# switchesbrd.net
KiCad netlist of a schematic drawn in EAGLE
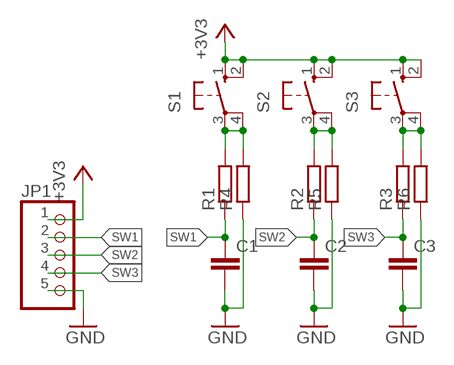
[diagram p0: schematic, sheet 1]

(export (version "E")
  (design (tool "Eeschema 10.0.6"))
  (components
    (comp (ref "C1")
      (value "C-EU025-025X050")
      (footprint "eagle-import:C025-025X050")
      (libsource (lib "eagle-import") (part "C-EU025-025X050"))
    )
    (comp (ref "C2")
      (value "C-EU025-025X050")
      (footprint "eagle-import:C025-025X050")
      (libsource (lib "eagle-import") (part "C-EU025-025X050"))
    )
    (comp (ref "C3")
      (value "C-EU025-025X050")
      (footprint "eagle-import:C025-025X050")
      (libsource (lib "eagle-import") (part "C-EU025-025X050"))
    )
    (comp (ref "JP1")
      (value "PINHD-1X5")
      (footprint "eagle-import:1X05")
      (libsource (lib "eagle-import") (part "PINHD-1X5"))
    )
    (comp (ref "R1")
      (value "R-EU_0204/5")
      (footprint "eagle-import:0204_5")
      (libsource (lib "eagle-import") (part "R-EU_0204/5"))
    )
    (comp (ref "R2")
      (value "R-EU_0204/5")
      (footprint "eagle-import:0204_5")
      (libsource (lib "eagle-import") (part "R-EU_0204/5"))
    )
    (comp (ref "R3")
      (value "R-EU_0204/5")
      (footprint "eagle-import:0204_5")
      (libsource (lib "eagle-import") (part "R-EU_0204/5"))
    )
    (comp (ref "R4")
      (value "R-EU_0204/5")
      (footprint "eagle-import:0204_5")
      (libsource (lib "eagle-import") (part "R-EU_0204/5"))
    )
    (comp (ref "R5")
      (value "R-EU_0204/5")
      (footprint "eagle-import:0204_5")
      (libsource (lib "eagle-import") (part "R-EU_0204/5"))
    )
    (comp (ref "R6")
      (value "R-EU_0204/5")
      (footprint "eagle-import:0204_5")
      (libsource (lib "eagle-import") (part "R-EU_0204/5"))
    )
    (comp (ref "S1")
      (value "10-XX")
      (footprint "eagle-import:B3F-10XX")
      (fields (field (name "MPN") "B3F-1000"))
      (libsource (lib "eagle-import") (part "10-XX"))
    )
    (comp (ref "S2")
      (value "10-XX")
      (footprint "eagle-import:B3F-10XX")
      (fields (field (name "MPN") "B3F-1000"))
      (libsource (lib "eagle-import") (part "10-XX"))
    )
    (comp (ref "S3")
      (value "10-XX")
      (footprint "eagle-import:B3F-10XX")
      (fields (field (name "MPN") "B3F-1000"))
      (libsource (lib "eagle-import") (part "10-XX"))
    )
  )
  (nets
    (net (code "1") (name "+3V3") (class "Default")
      (node (ref "JP1") (pin "1") (pinfunction "1_1") (pintype "passive"))
      (node (ref "S1") (pin "1") (pinfunction "S_1") (pintype "passive"))
      (node (ref "S1") (pin "2") (pinfunction "S1_2") (pintype "passive"))
      (node (ref "S2") (pin "1") (pinfunction "S_1") (pintype "passive"))
      (node (ref "S2") (pin "2") (pinfunction "S1_2") (pintype "passive"))
      (node (ref "S3") (pin "1") (pinfunction "S_1") (pintype "passive"))
      (node (ref "S3") (pin "2") (pinfunction "S1_2") (pintype "passive"))
    )
    (net (code "2") (name "GND") (class "Default")
      (node (ref "C1") (pin "2") (pinfunction "2_2") (pintype "passive"))
      (node (ref "C2") (pin "2") (pinfunction "2_2") (pintype "passive"))
      (node (ref "C3") (pin "2") (pinfunction "2_2") (pintype "passive"))
      (node (ref "JP1") (pin "5") (pinfunction "5_5") (pintype "passive"))
      (node (ref "R4") (pin "1") (pinfunction "1_1") (pintype "passive"))
      (node (ref "R5") (pin "1") (pinfunction "1_1") (pintype "passive"))
      (node (ref "R6") (pin "1") (pinfunction "1_1") (pintype "passive"))
    )
    (net (code "3") (name "Net-(S1-P)") (class "Default")
      (node (ref "R1") (pin "2") (pinfunction "2_2") (pintype "passive"))
      (node (ref "R4") (pin "2") (pinfunction "2_2") (pintype "passive"))
      (node (ref "S1") (pin "3") (pinfunction "P_3") (pintype "passive"))
      (node (ref "S1") (pin "4") (pinfunction "P1_4") (pintype "passive"))
    )
    (net (code "4") (name "Net-(S2-P)") (class "Default")
      (node (ref "R2") (pin "2") (pinfunction "2_2") (pintype "passive"))
      (node (ref "R5") (pin "2") (pinfunction "2_2") (pintype "passive"))
      (node (ref "S2") (pin "3") (pinfunction "P_3") (pintype "passive"))
      (node (ref "S2") (pin "4") (pinfunction "P1_4") (pintype "passive"))
    )
    (net (code "5") (name "Net-(S3-P)") (class "Default")
      (node (ref "R3") (pin "2") (pinfunction "2_2") (pintype "passive"))
      (node (ref "R6") (pin "2") (pinfunction "2_2") (pintype "passive"))
      (node (ref "S3") (pin "3") (pinfunction "P_3") (pintype "passive"))
      (node (ref "S3") (pin "4") (pinfunction "P1_4") (pintype "passive"))
    )
    (net (code "6") (name "SW1") (class "Default")
      (node (ref "C1") (pin "1") (pinfunction "1_1") (pintype "passive"))
      (node (ref "JP1") (pin "2") (pinfunction "2_2") (pintype "passive"))
      (node (ref "R1") (pin "1") (pinfunction "1_1") (pintype "passive"))
    )
    (net (code "7") (name "SW2") (class "Default")
      (node (ref "C2") (pin "1") (pinfunction "1_1") (pintype "passive"))
      (node (ref "JP1") (pin "3") (pinfunction "3_3") (pintype "passive"))
      (node (ref "R2") (pin "1") (pinfunction "1_1") (pintype "passive"))
    )
    (net (code "8") (name "SW3") (class "Default")
      (node (ref "C3") (pin "1") (pinfunction "1_1") (pintype "passive"))
      (node (ref "JP1") (pin "4") (pinfunction "4_4") (pintype "passive"))
      (node (ref "R3") (pin "1") (pinfunction "1_1") (pintype "passive"))
    )
  )
)
